# EE474FINAL.net
KiCad netlist of a schematic drawn in EAGLE
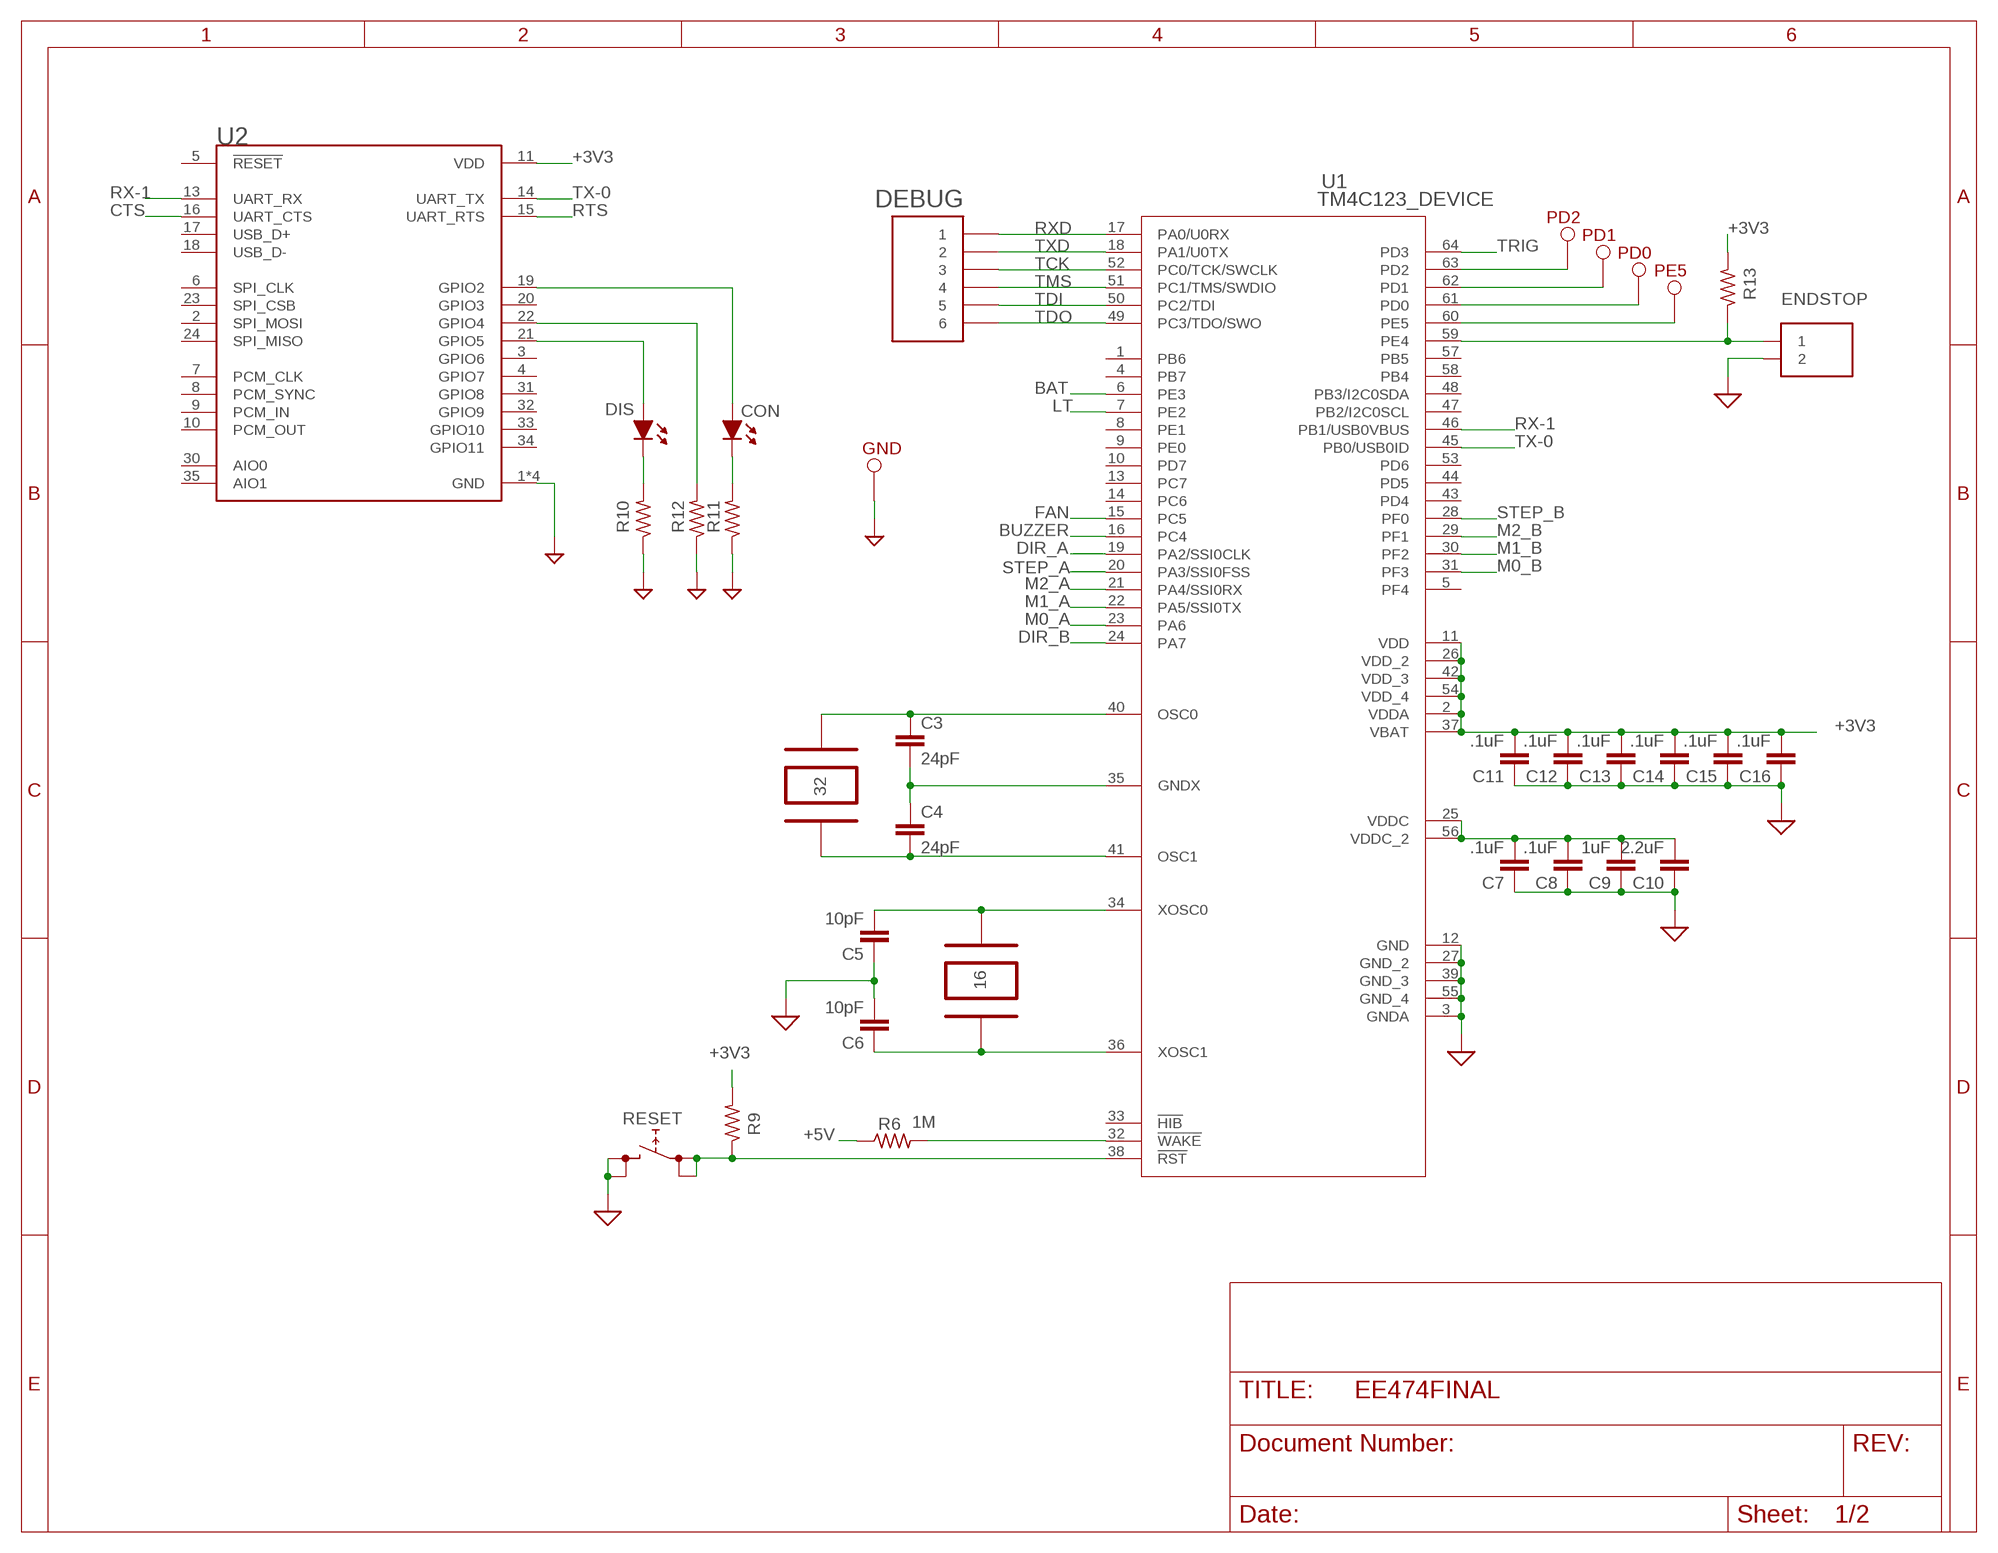
[diagram p0: schematic, sheet 1]
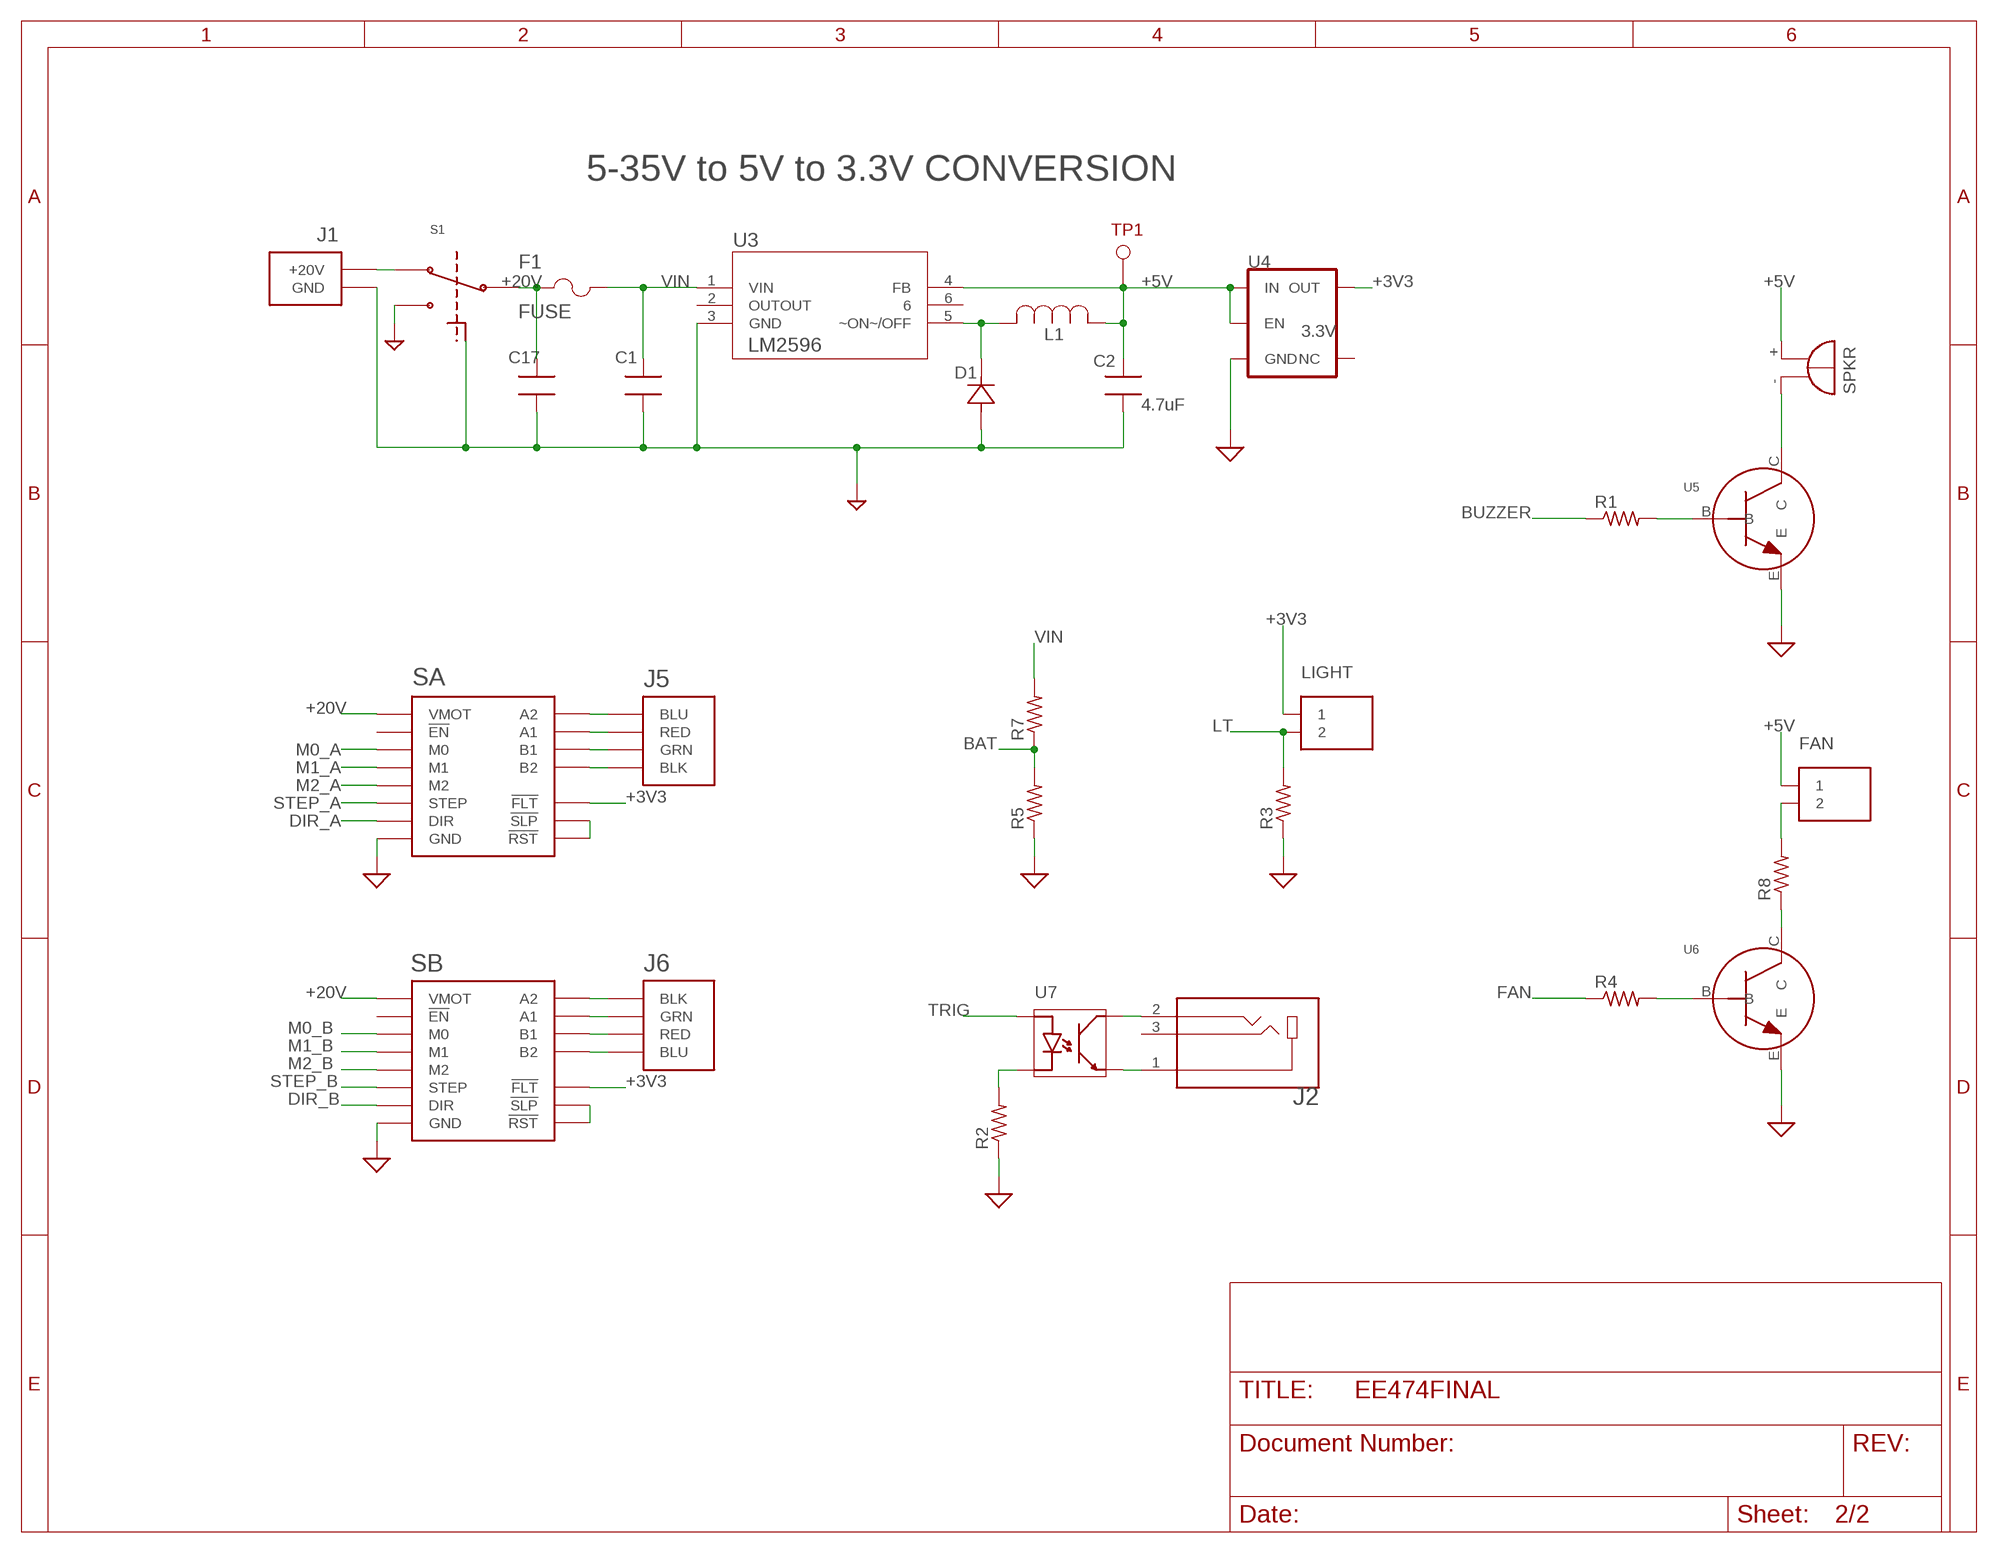
[diagram p1: schematic, sheet 2]

(export (version "E")
  (design (tool "Eeschema 10.0.6"))
  (components
    (comp (ref "C3")
      (value "24pF")
      (footprint "eagle-import:CAPC1005X35N")
      (libsource (lib "eagle-import") (part "CAPACITOR"))
    )
    (comp (ref "C4")
      (value "24pF")
      (footprint "eagle-import:CAPC1005X35N")
      (libsource (lib "eagle-import") (part "CAPACITOR"))
    )
    (comp (ref "C5")
      (value "10pF")
      (footprint "eagle-import:CAPC1005X35N")
      (libsource (lib "eagle-import") (part "CAPACITOR"))
    )
    (comp (ref "C6")
      (value "10pF")
      (footprint "eagle-import:CAPC1005X35N")
      (libsource (lib "eagle-import") (part "CAPACITOR"))
    )
    (comp (ref "C7")
      (value ".1uF")
      (footprint "eagle-import:CAPC1005X35N")
      (libsource (lib "eagle-import") (part "CAPACITOR"))
    )
    (comp (ref "C8")
      (value ".1uF")
      (footprint "eagle-import:CAPC1005X35N")
      (libsource (lib "eagle-import") (part "CAPACITOR"))
    )
    (comp (ref "C9")
      (value "1uF")
      (footprint "eagle-import:CAPC1005X35N")
      (libsource (lib "eagle-import") (part "CAPACITOR"))
    )
    (comp (ref "C10")
      (value "2.2uF")
      (footprint "eagle-import:CAPC1005X35N")
      (libsource (lib "eagle-import") (part "CAPACITOR"))
    )
    (comp (ref "C11")
      (value ".1uF")
      (footprint "eagle-import:CAPC1005X35N")
      (libsource (lib "eagle-import") (part "CAPACITOR"))
    )
    (comp (ref "C12")
      (value ".1uF")
      (footprint "eagle-import:CAPC1005X35N")
      (libsource (lib "eagle-import") (part "CAPACITOR"))
    )
    (comp (ref "C13")
      (value ".1uF")
      (footprint "eagle-import:CAPC1005X35N")
      (libsource (lib "eagle-import") (part "CAPACITOR"))
    )
    (comp (ref "C14")
      (value ".1uF")
      (footprint "eagle-import:CAPC1005X35N")
      (libsource (lib "eagle-import") (part "CAPACITOR"))
    )
    (comp (ref "C15")
      (value ".1uF")
      (footprint "eagle-import:CAPC1005X35N")
      (libsource (lib "eagle-import") (part "CAPACITOR"))
    )
    (comp (ref "C16")
      (value ".1uF")
      (footprint "eagle-import:CAPC1005X35N")
      (libsource (lib "eagle-import") (part "CAPACITOR"))
    )
    (comp (ref "CON")
      (value "LED_511")
      (footprint "eagle-import:LED_511")
      (libsource (lib "eagle-import") (part "LED_511"))
    )
    (comp (ref "DEBUG")
      (value "6POS_JST")
      (footprint "eagle-import:6POS_JST")
      (fields (field (name "MANUFACTURER_PART_NUMBER") "S6BZRLFSN"))
      (libsource (lib "eagle-import") (part "6POS_JST"))
    )
    (comp (ref "DIS")
      (value "LED_511")
      (footprint "eagle-import:LED_511")
      (libsource (lib "eagle-import") (part "LED_511"))
    )
    (comp (ref "ENDSTOP")
      (value "2POS_JSTVERT_2.0")
      (footprint "eagle-import:2POS_JSTVERT_2.00")
      (libsource (lib "eagle-import") (part "2POS_JSTVERT_2.0"))
    )
    (comp (ref "GND")
      (value "TESTPOINT")
      (footprint "eagle-import:TESTPOINT")
      (libsource (lib "eagle-import") (part "TESTPOINT"))
    )
    (comp (ref "PD0")
      (value "TESTPOINT")
      (footprint "eagle-import:TESTPOINT")
      (libsource (lib "eagle-import") (part "TESTPOINT"))
    )
    (comp (ref "PD1")
      (value "TESTPOINT")
      (footprint "eagle-import:TESTPOINT")
      (libsource (lib "eagle-import") (part "TESTPOINT"))
    )
    (comp (ref "PD2")
      (value "TESTPOINT")
      (footprint "eagle-import:TESTPOINT")
      (libsource (lib "eagle-import") (part "TESTPOINT"))
    )
    (comp (ref "PE5")
      (value "TESTPOINT")
      (footprint "eagle-import:TESTPOINT")
      (libsource (lib "eagle-import") (part "TESTPOINT"))
    )
    (comp (ref "R6")
      (value "1M")
      (footprint "eagle-import:CAPC1005X35N")
      (libsource (lib "eagle-import") (part "RESISTOR"))
    )
    (comp (ref "R9")
      (value "RESISTOR")
      (footprint "eagle-import:CAPC1005X35N")
      (libsource (lib "eagle-import") (part "RESISTOR"))
    )
    (comp (ref "R10")
      (value "RESISTOR")
      (footprint "eagle-import:CAPC1005X35N")
      (libsource (lib "eagle-import") (part "RESISTOR"))
    )
    (comp (ref "R11")
      (value "RESISTOR")
      (footprint "eagle-import:CAPC1005X35N")
      (libsource (lib "eagle-import") (part "RESISTOR"))
    )
    (comp (ref "R12")
      (value "RESISTOR")
      (footprint "eagle-import:CAPC1005X35N")
      (libsource (lib "eagle-import") (part "RESISTOR"))
    )
    (comp (ref "R13")
      (value "RESISTOR")
      (footprint "eagle-import:CAPC1005X35N")
      (libsource (lib "eagle-import") (part "RESISTOR"))
    )
    (comp (ref "RESET")
      (value "SWITCH_B3S")
      (footprint "eagle-import:SW_BS3")
      (libsource (lib "eagle-import") (part "SWITCH_B3S"))
    )
    (comp (ref "U1")
      (value "TM4C123_DEVICE")
      (footprint "eagle-import:TM3C123_FOOTPRINT")
      (libsource (lib "eagle-import") (part "TM4C123_DEVICE"))
    )
    (comp (ref "U2")
      (value "RN42-I/RM")
      (footprint "eagle-import:XCVR_RN42-I_RM")
      (fields (field (name "DIGI-KEY_PART_NUMBER") "740-1038-ND") (field (name "MF") "Microchip"))
      (libsource (lib "eagle-import") (part "RN42-I/RM"))
    )
    (comp (ref "Y1")
      (value "32kHz")
      (footprint "eagle-import:GHI2_CRYSTAL_3.2X1.5")
      (libsource (lib "eagle-import") (part "32KHZ_OSCILATOR"))
    )
    (comp (ref "Y2")
      (value "Y2")
      (footprint "eagle-import:CRYSTAL_16MHZ")
      (libsource (lib "eagle-import") (part "16MHZ_OSCILLATOR"))
    )
    (comp (ref "C1")
      (value "CAP_18")
      (footprint "eagle-import:CAP_ULH_10X10")
      (fields (field (name "MANUFACTURER_PART_NUMBER") "ULT2D180MNL1GS"))
      (libsource (lib "eagle-import") (part "CAP_18"))
    )
    (comp (ref "C2")
      (value "4.7uF")
      (footprint "eagle-import:CAP_UCD_8X6P2")
      (fields (field (name "MANUFACTURER_PART_NUMBER") "UUX2A4R7MCL1GS"))
      (libsource (lib "eagle-import") (part "CAP_4.7"))
    )
    (comp (ref "C17")
      (value "CAP_18")
      (footprint "eagle-import:CAP_ULH_10X10")
      (fields (field (name "MANUFACTURER_PART_NUMBER") "ULT2D180MNL1GS"))
      (libsource (lib "eagle-import") (part "CAP_18"))
    )
    (comp (ref "D1")
      (value "DIODE_SHOTKY_SMA")
      (footprint "eagle-import:SMA")
      (fields (field (name "MANUFACTURER_PART_NUMBER") "S1M13F"))
      (libsource (lib "eagle-import") (part "DIODE_SHOTKY_SMA"))
    )
    (comp (ref "F1")
      (value "FUSE")
      (footprint "eagle-import:FUS_VISHAY_MFU0805")
      (fields (field (name "MANUFACTURER_PART_NUMBER") "MFU0805FF02000P100"))
      (libsource (lib "eagle-import") (part "FUSE"))
    )
    (comp (ref "FAN")
      (value "2POS_JSTVERT_2.0")
      (footprint "eagle-import:2POS_JSTVERT_2.00")
      (libsource (lib "eagle-import") (part "2POS_JSTVERT_2.0"))
    )
    (comp (ref "J1")
      (value "2POS_JSTVERT_2.5")
      (footprint "eagle-import:2POS_JSTVERT")
      (libsource (lib "eagle-import") (part "2POS_JSTVERT_2.5"))
    )
    (comp (ref "J2")
      (value "AUDIOJACK")
      (footprint "eagle-import:AUDIOJACK")
      (fields (field (name "MF") "CUI Devices") (field (name "MP") "SJ1-3523N"))
      (libsource (lib "eagle-import") (part "AUDIOJACK"))
    )
    (comp (ref "J5")
      (value "4POS_MOLEXVERT")
      (footprint "eagle-import:4POS_MOLEXVERT")
      (libsource (lib "eagle-import") (part "4POS_MOLEXVERT"))
    )
    (comp (ref "J6")
      (value "4POS_MOLEX_2.54")
      (footprint "eagle-import:MOLEX_0705530003")
      (libsource (lib "eagle-import") (part "4POS_MOLEX_2.54"))
    )
    (comp (ref "L1")
      (value "INDUCTOR_SRR1210-680M")
      (footprint "eagle-import:IND_BOURNS_SRR1210")
      (fields (field (name "MANUFACTURER_PART_NUMBER") "SRR1210680M"))
      (libsource (lib "eagle-import") (part "INDUCTOR_SRR1210-680M"))
    )
    (comp (ref "LIGHT")
      (value "2POS_JSTVERT_2.0")
      (footprint "eagle-import:2POS_JSTVERT_2.00")
      (libsource (lib "eagle-import") (part "2POS_JSTVERT_2.0"))
    )
    (comp (ref "R1")
      (value "R-US_R0402")
      (footprint "eagle-import:R0402")
      (libsource (lib "eagle-import") (part "R-US_R0402"))
    )
    (comp (ref "R2")
      (value "R-US_R0402")
      (footprint "eagle-import:R0402")
      (libsource (lib "eagle-import") (part "R-US_R0402"))
    )
    (comp (ref "R3")
      (value "R-US_R0402")
      (footprint "eagle-import:R0402")
      (libsource (lib "eagle-import") (part "R-US_R0402"))
    )
    (comp (ref "R4")
      (value "R-US_R0402")
      (footprint "eagle-import:R0402")
      (libsource (lib "eagle-import") (part "R-US_R0402"))
    )
    (comp (ref "R5")
      (value "R-US_R0402")
      (footprint "eagle-import:R0402")
      (libsource (lib "eagle-import") (part "R-US_R0402"))
    )
    (comp (ref "R7")
      (value "R-US_R0402")
      (footprint "eagle-import:R0402")
      (libsource (lib "eagle-import") (part "R-US_R0402"))
    )
    (comp (ref "R8")
      (value "R-US_R0402")
      (footprint "eagle-import:R0402")
      (libsource (lib "eagle-import") (part "R-US_R0402"))
    )
    (comp (ref "S1")
      (value "SLIDESWITCH")
      (footprint "eagle-import:SLIDESWITCH")
      (libsource (lib "eagle-import") (part "SLIDESWITCH"))
    )
    (comp (ref "SA")
      (value "DRV8825")
      (footprint "eagle-import:DRV8825")
      (libsource (lib "eagle-import") (part "DRV8825"))
    )
    (comp (ref "SB")
      (value "DRV8825")
      (footprint "eagle-import:DRV8825")
      (libsource (lib "eagle-import") (part "DRV8825"))
    )
    (comp (ref "SPKR")
      (value "F/QMBIII")
      (footprint "eagle-import:F_QMBIII")
      (libsource (lib "eagle-import") (part "F/QMBIII"))
    )
    (comp (ref "TP1")
      (value "TESTPOINT")
      (footprint "eagle-import:TESTPOINT")
      (libsource (lib "eagle-import") (part "TESTPOINT"))
    )
    (comp (ref "U3")
      (value "LM2596SX-5.0/NOPB")
      (footprint "eagle-import:TS5B")
      (fields (field (name "MANUFACTURER_PART_NUMBER") "LM2596SX5.0NOPB"))
      (libsource (lib "eagle-import") (part "LM2596SX-5.0/NOPB"))
    )
    (comp (ref "U4")
      (value "3.3V")
      (footprint "eagle-import:SOT23-5")
      (libsource (lib "eagle-import") (part "V_REG_AP2112K-3.3V"))
    )
    (comp (ref "U5")
      (value "NPN_BJT")
      (footprint "eagle-import:SOT-23")
      (libsource (lib "eagle-import") (part "NPN_BJT"))
    )
    (comp (ref "U6")
      (value "NPN_BJT")
      (footprint "eagle-import:SOT-23")
      (libsource (lib "eagle-import") (part "NPN_BJT"))
    )
    (comp (ref "U7")
      (value "OPTOISOLATOR")
      (footprint "eagle-import:SOP-4L_TC")
      (libsource (lib "eagle-import") (part "OPTOISOLATOR"))
    )
  )
  (nets
    (net (code "1") (name "+3V3") (class "Default")
      (node (ref "C11") (pin "2") (pinfunction "2_2") (pintype "passive"))
      (node (ref "C12") (pin "2") (pinfunction "2_2") (pintype "passive"))
      (node (ref "C13") (pin "2") (pinfunction "2_2") (pintype "passive"))
      (node (ref "C14") (pin "2") (pinfunction "2_2") (pintype "passive"))
      (node (ref "C15") (pin "2") (pinfunction "2_2") (pintype "passive"))
      (node (ref "C16") (pin "2") (pinfunction "2_2") (pintype "passive"))
      (node (ref "LIGHT") (pin "1") (pinfunction "1_1") (pintype "bidirectional"))
      (node (ref "R13") (pin "2") (pinfunction "2_2") (pintype "passive"))
      (node (ref "R9") (pin "2") (pinfunction "2_2") (pintype "passive"))
      (node (ref "SA") (pin "!FLT") (pinfunction "~{FLT}_!FLT") (pintype "bidirectional"))
      (node (ref "SB") (pin "!FLT") (pinfunction "~{FLT}_!FLT") (pintype "bidirectional"))
      (node (ref "U1") (pin "11") (pinfunction "VDD_11") (pintype "power_in"))
      (node (ref "U1") (pin "2") (pinfunction "VDDA_2") (pintype "power_in"))
      (node (ref "U1") (pin "26") (pinfunction "VDD_2_26") (pintype "power_in"))
      (node (ref "U1") (pin "37") (pinfunction "VBAT_37") (pintype "power_in"))
      (node (ref "U1") (pin "42") (pinfunction "VDD_3_42") (pintype "power_in"))
      (node (ref "U1") (pin "54") (pinfunction "VDD_4_54") (pintype "power_in"))
      (node (ref "U2") (pin "11") (pinfunction "VDD_11") (pintype "power_in"))
      (node (ref "U4") (pin "5") (pinfunction "OUT_5") (pintype "passive"))
    )
    (net (code "2") (name "+5V") (class "Default")
      (node (ref "C2") (pin "1") (pinfunction "1_1") (pintype "passive"))
      (node (ref "FAN") (pin "1") (pinfunction "1_1") (pintype "bidirectional"))
      (node (ref "L1") (pin "1") (pinfunction "1_1") (pintype "passive"))
      (node (ref "R6") (pin "1") (pinfunction "1_1") (pintype "passive"))
      (node (ref "SPKR") (pin "+") (pinfunction "-_+") (pintype "passive"))
      (node (ref "TP1") (pin "P$1") (pinfunction "P$1_P$1") (pintype "bidirectional"))
      (node (ref "U3") (pin "4") (pinfunction "FB_4") (pintype "passive"))
      (node (ref "U4") (pin "1") (pinfunction "IN_1") (pintype "input"))
      (node (ref "U4") (pin "3") (pinfunction "EN_3") (pintype "input"))
    )
    (net (code "3") (name "+20V") (class "Default")
      (node (ref "C17") (pin "1") (pinfunction "1_1") (pintype "passive"))
      (node (ref "F1") (pin "1") (pinfunction "1_1") (pintype "passive"))
      (node (ref "S1") (pin "2") (pinfunction "2_2") (pintype "passive"))
      (node (ref "SA") (pin "VMOT") (pinfunction "VMOT_VMOT") (pintype "bidirectional"))
      (node (ref "SB") (pin "VMOT") (pinfunction "VMOT_VMOT") (pintype "bidirectional"))
    )
    (net (code "4") (name "BAT") (class "Default")
      (node (ref "R5") (pin "2") (pinfunction "2_2") (pintype "passive"))
      (node (ref "R7") (pin "1") (pinfunction "1_1") (pintype "passive"))
      (node (ref "U1") (pin "6") (pinfunction "PE3_6") (pintype "bidirectional"))
    )
    (net (code "5") (name "BUZZER") (class "Default")
      (node (ref "R1") (pin "1") (pinfunction "1_1") (pintype "passive"))
      (node (ref "U1") (pin "16") (pinfunction "PC4_16") (pintype "bidirectional"))
    )
    (net (code "6") (name "CTS") (class "Default")
      (node (ref "U2") (pin "16") (pinfunction "UART_CTS_16") (pintype "input"))
    )
    (net (code "7") (name "DIR_A") (class "Default")
      (node (ref "SA") (pin "DIR") (pinfunction "DIR_DIR") (pintype "bidirectional"))
      (node (ref "U1") (pin "19") (pinfunction "PA2/SSI0CLK_19") (pintype "bidirectional"))
    )
    (net (code "8") (name "DIR_B") (class "Default")
      (node (ref "SB") (pin "DIR") (pinfunction "DIR_DIR") (pintype "bidirectional"))
      (node (ref "U1") (pin "24") (pinfunction "PA7_24") (pintype "bidirectional"))
    )
    (net (code "9") (name "FAN") (class "Default")
      (node (ref "R4") (pin "1") (pinfunction "1_1") (pintype "passive"))
      (node (ref "U1") (pin "15") (pinfunction "PC5_15") (pintype "bidirectional"))
    )
    (net (code "10") (name "GND") (class "Default")
      (node (ref "C1") (pin "2") (pinfunction "2_2") (pintype "passive"))
      (node (ref "C10") (pin "1") (pinfunction "1_1") (pintype "passive"))
      (node (ref "C11") (pin "1") (pinfunction "1_1") (pintype "passive"))
      (node (ref "C12") (pin "1") (pinfunction "1_1") (pintype "passive"))
      (node (ref "C13") (pin "1") (pinfunction "1_1") (pintype "passive"))
      (node (ref "C14") (pin "1") (pinfunction "1_1") (pintype "passive"))
      (node (ref "C15") (pin "1") (pinfunction "1_1") (pintype "passive"))
      (node (ref "C16") (pin "1") (pinfunction "1_1") (pintype "passive"))
      (node (ref "C17") (pin "2") (pinfunction "2_2") (pintype "passive"))
      (node (ref "C2") (pin "2") (pinfunction "2_2") (pintype "passive"))
      (node (ref "C5") (pin "1") (pinfunction "1_1") (pintype "passive"))
      (node (ref "C6") (pin "2") (pinfunction "2_2") (pintype "passive"))
      (node (ref "C7") (pin "1") (pinfunction "1_1") (pintype "passive"))
      (node (ref "C8") (pin "1") (pinfunction "1_1") (pintype "passive"))
      (node (ref "C9") (pin "1") (pinfunction "1_1") (pintype "passive"))
      (node (ref "D1") (pin "2") (pinfunction "2_2") (pintype "passive"))
      (node (ref "ENDSTOP") (pin "2") (pinfunction "2_2") (pintype "bidirectional"))
      (node (ref "GND") (pin "P$1") (pinfunction "P$1_P$1") (pintype "bidirectional"))
      (node (ref "J1") (pin "P$2") (pinfunction "GND_P$2") (pintype "passive"))
      (node (ref "R10") (pin "1") (pinfunction "1_1") (pintype "passive"))
      (node (ref "R11") (pin "1") (pinfunction "1_1") (pintype "passive"))
      (node (ref "R12") (pin "1") (pinfunction "1_1") (pintype "passive"))
      (node (ref "R2") (pin "1") (pinfunction "1_1") (pintype "passive"))
      (node (ref "R3") (pin "1") (pinfunction "1_1") (pintype "passive"))
      (node (ref "R5") (pin "1") (pinfunction "1_1") (pintype "passive"))
      (node (ref "RESET") (pin "3") (pinfunction "3_3") (pintype "passive"))
      (node (ref "RESET") (pin "4") (pinfunction "4_4") (pintype "passive"))
      (node (ref "S1") (pin "3") (pinfunction "3_3") (pintype "passive"))
      (node (ref "S1") (pin "4") (pinfunction "GND_4") (pintype "passive"))
      (node (ref "S1") (pin "5") (pinfunction "GND_5") (pintype "passive"))
      (node (ref "SA") (pin "GND$1") (pinfunction "GND_GND$1") (pintype "bidirectional"))
      (node (ref "SA") (pin "GND$2") (pinfunction "GND_GND$2") (pintype "bidirectional"))
      (node (ref "SB") (pin "GND$1") (pinfunction "GND_GND$1") (pintype "bidirectional"))
      (node (ref "SB") (pin "GND$2") (pinfunction "GND_GND$2") (pintype "bidirectional"))
      (node (ref "U1") (pin "12") (pinfunction "GND_12") (pintype "power_in"))
      (node (ref "U1") (pin "27") (pinfunction "GND_2_27") (pintype "power_in"))
      (node (ref "U1") (pin "3") (pinfunction "GNDA_3") (pintype "power_in"))
      (node (ref "U1") (pin "39") (pinfunction "GND_3_39") (pintype "power_in"))
      (node (ref "U1") (pin "55") (pinfunction "GND_4_55") (pintype "power_in"))
      (node (ref "U2") (pin "1") (pinfunction "GND_1") (pintype "power_in"))
      (node (ref "U2") (pin "12") (pinfunction "GND_12") (pintype "power_in"))
      (node (ref "U2") (pin "28") (pinfunction "GND_28") (pintype "power_in"))
      (node (ref "U2") (pin "29") (pinfunction "GND_29") (pintype "power_in"))
      (node (ref "U3") (pin "3") (pinfunction "GND_3") (pintype "passive"))
      (node (ref "U4") (pin "2") (pinfunction "GND_2") (pintype "input"))
      (node (ref "U5") (pin "E") (pinfunction "E_E") (pintype "bidirectional"))
      (node (ref "U6") (pin "E") (pinfunction "E_E") (pintype "bidirectional"))
    )
    (net (code "11") (name "LT") (class "Default")
      (node (ref "LIGHT") (pin "2") (pinfunction "2_2") (pintype "bidirectional"))
      (node (ref "R3") (pin "2") (pinfunction "2_2") (pintype "passive"))
      (node (ref "U1") (pin "7") (pinfunction "PE2_7") (pintype "bidirectional"))
    )
    (net (code "12") (name "M0_A") (class "Default")
      (node (ref "SA") (pin "M0") (pinfunction "M0_M0") (pintype "bidirectional"))
      (node (ref "U1") (pin "23") (pinfunction "PA6_23") (pintype "bidirectional"))
    )
    (net (code "13") (name "M0_B") (class "Default")
      (node (ref "SB") (pin "M0") (pinfunction "M0_M0") (pintype "bidirectional"))
      (node (ref "U1") (pin "31") (pinfunction "PF3_31") (pintype "bidirectional"))
    )
    (net (code "14") (name "M1_A") (class "Default")
      (node (ref "SA") (pin "M1") (pinfunction "M1_M1") (pintype "bidirectional"))
      (node (ref "U1") (pin "22") (pinfunction "PA5/SSI0TX_22") (pintype "bidirectional"))
    )
    (net (code "15") (name "M1_B") (class "Default")
      (node (ref "SB") (pin "M1") (pinfunction "M1_M1") (pintype "bidirectional"))
      (node (ref "U1") (pin "30") (pinfunction "PF2_30") (pintype "bidirectional"))
    )
    (net (code "16") (name "M2_A") (class "Default")
      (node (ref "SA") (pin "M2") (pinfunction "M2_M2") (pintype "bidirectional"))
      (node (ref "U1") (pin "21") (pinfunction "PA4/SSI0RX_21") (pintype "bidirectional"))
    )
    (net (code "17") (name "M2_B") (class "Default")
      (node (ref "SB") (pin "M2") (pinfunction "M2_M2") (pintype "bidirectional"))
      (node (ref "U1") (pin "29") (pinfunction "PF1_29") (pintype "bidirectional"))
    )
    (net (code "18") (name "Net-(CON-1)") (class "Default")
      (node (ref "CON") (pin "P$1") (pinfunction "1_P$1") (pintype "bidirectional"))
      (node (ref "R11") (pin "2") (pinfunction "2_2") (pintype "passive"))
    )
    (net (code "19") (name "Net-(CON-2)") (class "Default")
      (node (ref "CON") (pin "P$2") (pinfunction "2_P$2") (pintype "bidirectional"))
      (node (ref "U2") (pin "19") (pinfunction "GPIO2_19") (pintype "bidirectional"))
    )
    (net (code "20") (name "Net-(DIS-1)") (class "Default")
      (node (ref "DIS") (pin "P$1") (pinfunction "1_P$1") (pintype "bidirectional"))
      (node (ref "R10") (pin "2") (pinfunction "2_2") (pintype "passive"))
    )
    (net (code "21") (name "Net-(DIS-2)") (class "Default")
      (node (ref "DIS") (pin "P$2") (pinfunction "2_P$2") (pintype "bidirectional"))
      (node (ref "U2") (pin "21") (pinfunction "GPIO5_21") (pintype "bidirectional"))
    )
    (net (code "22") (name "Net-(FAN-Pad2)") (class "Default")
      (node (ref "FAN") (pin "2") (pinfunction "2_2") (pintype "bidirectional"))
      (node (ref "R8") (pin "2") (pinfunction "2_2") (pintype "passive"))
    )
    (net (code "23") (name "Net-(J1-+20V)") (class "Default")
      (node (ref "J1") (pin "P$1") (pinfunction "+20V_P$1") (pintype "passive"))
      (node (ref "S1") (pin "1") (pinfunction "1_1") (pintype "passive"))
    )
    (net (code "24") (name "Net-(J2-Pad1)") (class "Default")
      (node (ref "J2") (pin "1") (pinfunction "1_1") (pintype "passive"))
      (node (ref "U7") (pin "3") (pinfunction "3_3") (pintype "bidirectional"))
    )
    (net (code "25") (name "Net-(J2-Pad2)") (class "Default")
      (node (ref "J2") (pin "2") (pinfunction "2_2") (pintype "passive"))
      (node (ref "U7") (pin "4") (pinfunction "4_4") (pintype "bidirectional"))
    )
    (net (code "26") (name "Net-(J5-BLK)") (class "Default")
      (node (ref "J5") (pin "P$1") (pinfunction "BLK_P$1") (pintype "bidirectional"))
      (node (ref "SA") (pin "B2") (pinfunction "B2_B2") (pintype "bidirectional"))
    )
    (net (code "27") (name "Net-(J5-BLU)") (class "Default")
      (node (ref "J5") (pin "P$4") (pinfunction "BLU_P$4") (pintype "bidirectional"))
      (node (ref "SA") (pin "A2") (pinfunction "A2_A2") (pintype "bidirectional"))
    )
    (net (code "28") (name "Net-(J5-GRN)") (class "Default")
      (node (ref "J5") (pin "P$2") (pinfunction "GRN_P$2") (pintype "bidirectional"))
      (node (ref "SA") (pin "B1") (pinfunction "B1_B1") (pintype "bidirectional"))
    )
    (net (code "29") (name "Net-(J5-RED)") (class "Default")
      (node (ref "J5") (pin "P$3") (pinfunction "RED_P$3") (pintype "bidirectional"))
      (node (ref "SA") (pin "A1") (pinfunction "A1_A1") (pintype "bidirectional"))
    )
    (net (code "30") (name "Net-(J6-BLK)") (class "Default")
      (node (ref "J6") (pin "4") (pinfunction "BLK_4") (pintype "bidirectional"))
      (node (ref "SB") (pin "A2") (pinfunction "A2_A2") (pintype "bidirectional"))
    )
    (net (code "31") (name "Net-(J6-BLU)") (class "Default")
      (node (ref "J6") (pin "1") (pinfunction "BLU_1") (pintype "bidirectional"))
      (node (ref "SB") (pin "B2") (pinfunction "B2_B2") (pintype "bidirectional"))
    )
    (net (code "32") (name "Net-(J6-GRN)") (class "Default")
      (node (ref "J6") (pin "3") (pinfunction "GRN_3") (pintype "bidirectional"))
      (node (ref "SB") (pin "A1") (pinfunction "A1_A1") (pintype "bidirectional"))
    )
    (net (code "33") (name "Net-(J6-RED)") (class "Default")
      (node (ref "J6") (pin "2") (pinfunction "RED_2") (pintype "bidirectional"))
      (node (ref "SB") (pin "B1") (pinfunction "B1_B1") (pintype "bidirectional"))
    )
    (net (code "34") (name "Net-(R1-Pad2)") (class "Default")
      (node (ref "R1") (pin "2") (pinfunction "2_2") (pintype "passive"))
      (node (ref "U5") (pin "B") (pinfunction "B_B") (pintype "bidirectional"))
    )
    (net (code "35") (name "Net-(R2-Pad2)") (class "Default")
      (node (ref "R2") (pin "2") (pinfunction "2_2") (pintype "passive"))
      (node (ref "U7") (pin "2") (pinfunction "2_2") (pintype "bidirectional"))
    )
    (net (code "36") (name "Net-(R4-Pad2)") (class "Default")
      (node (ref "R4") (pin "2") (pinfunction "2_2") (pintype "passive"))
      (node (ref "U6") (pin "B") (pinfunction "B_B") (pintype "bidirectional"))
    )
    (net (code "37") (name "Net-(R8-Pad1)") (class "Default")
      (node (ref "R8") (pin "1") (pinfunction "1_1") (pintype "passive"))
      (node (ref "U6") (pin "C") (pinfunction "C_C") (pintype "bidirectional"))
    )
    (net (code "38") (name "Net-(SA-~{RST})") (class "Default")
      (node (ref "SA") (pin "!RST") (pinfunction "~{RST}_!RST") (pintype "bidirectional"))
      (node (ref "SA") (pin "!SLP") (pinfunction "~{SLP}_!SLP") (pintype "bidirectional"))
    )
    (net (code "39") (name "Net-(SB-~{RST})") (class "Default")
      (node (ref "SB") (pin "!RST") (pinfunction "~{RST}_!RST") (pintype "bidirectional"))
      (node (ref "SB") (pin "!SLP") (pinfunction "~{SLP}_!SLP") (pintype "bidirectional"))
    )
    (net (code "40") (name "Net-(SPKR-+)") (class "Default")
      (node (ref "SPKR") (pin "-") (pinfunction "+_-") (pintype "passive"))
      (node (ref "U5") (pin "C") (pinfunction "C_C") (pintype "bidirectional"))
    )
    (net (code "41") (name "Net-(U1-GNDX)") (class "Default")
      (node (ref "C3") (pin "2") (pinfunction "2_2") (pintype "passive"))
      (node (ref "C4") (pin "1") (pinfunction "1_1") (pintype "passive"))
      (node (ref "U1") (pin "35") (pinfunction "GNDX_35") (pintype "power_in"))
    )
    (net (code "42") (name "Net-(U1-OSC0)") (class "Default")
      (node (ref "C3") (pin "1") (pinfunction "1_1") (pintype "passive"))
      (node (ref "U1") (pin "40") (pinfunction "OSC0_40") (pintype "input"))
      (node (ref "Y1") (pin "P$2") (pinfunction "2_P$2") (pintype "passive"))
    )
    (net (code "43") (name "Net-(U1-OSC1)") (class "Default")
      (node (ref "C4") (pin "2") (pinfunction "2_2") (pintype "passive"))
      (node (ref "U1") (pin "41") (pinfunction "OSC1_41") (pintype "output"))
      (node (ref "Y1") (pin "P$1") (pinfunction "1_P$1") (pintype "passive"))
    )
    (net (code "44") (name "Net-(U1-PD0)") (class "Default")
      (node (ref "PD0") (pin "P$1") (pinfunction "P$1_P$1") (pintype "bidirectional"))
      (node (ref "U1") (pin "61") (pinfunction "PD0_61") (pintype "bidirectional"))
    )
    (net (code "45") (name "Net-(U1-PD1)") (class "Default")
      (node (ref "PD1") (pin "P$1") (pinfunction "P$1_P$1") (pintype "bidirectional"))
      (node (ref "U1") (pin "62") (pinfunction "PD1_62") (pintype "bidirectional"))
    )
    (net (code "46") (name "Net-(U1-PD2)") (class "Default")
      (node (ref "PD2") (pin "P$1") (pinfunction "P$1_P$1") (pintype "bidirectional"))
      (node (ref "U1") (pin "63") (pinfunction "PD2_63") (pintype "bidirectional"))
    )
    (net (code "47") (name "Net-(U1-PE4)") (class "Default")
      (node (ref "ENDSTOP") (pin "1") (pinfunction "1_1") (pintype "bidirectional"))
      (node (ref "R13") (pin "1") (pinfunction "1_1") (pintype "passive"))
      (node (ref "U1") (pin "59") (pinfunction "PE4_59") (pintype "bidirectional"))
    )
    (net (code "48") (name "Net-(U1-PE5)") (class "Default")
      (node (ref "PE5") (pin "P$1") (pinfunction "P$1_P$1") (pintype "bidirectional"))
      (node (ref "U1") (pin "60") (pinfunction "PE5_60") (pintype "bidirectional"))
    )
    (net (code "49") (name "Net-(U1-VDDC)") (class "Default")
      (node (ref "C10") (pin "2") (pinfunction "2_2") (pintype "passive"))
      (node (ref "C7") (pin "2") (pinfunction "2_2") (pintype "passive"))
      (node (ref "C8") (pin "2") (pinfunction "2_2") (pintype "passive"))
      (node (ref "C9") (pin "2") (pinfunction "2_2") (pintype "passive"))
      (node (ref "U1") (pin "25") (pinfunction "VDDC_25") (pintype "power_in"))
      (node (ref "U1") (pin "56") (pinfunction "VDDC_2_56") (pintype "power_in"))
    )
    (net (code "50") (name "Net-(U1-XOSC0)") (class "Default")
      (node (ref "C5") (pin "2") (pinfunction "2_2") (pintype "passive"))
      (node (ref "U1") (pin "34") (pinfunction "XOSC0_34") (pintype "input"))
      (node (ref "Y2") (pin "2") (pinfunction "2_2") (pintype "passive"))
    )
    (net (code "51") (name "Net-(U1-XOSC1)") (class "Default")
      (node (ref "C6") (pin "1") (pinfunction "1_1") (pintype "passive"))
      (node (ref "U1") (pin "36") (pinfunction "XOSC1_36") (pintype "output"))
      (node (ref "Y2") (pin "1") (pinfunction "1_1") (pintype "passive"))
    )
    (net (code "52") (name "Net-(U1-~{RST})") (class "Default")
      (node (ref "R9") (pin "1") (pinfunction "1_1") (pintype "passive"))
      (node (ref "RESET") (pin "1") (pinfunction "1_1") (pintype "passive"))
      (node (ref "RESET") (pin "2") (pinfunction "2_2") (pintype "passive"))
      (node (ref "U1") (pin "38") (pinfunction "~{RST}_38") (pintype "input"))
    )
    (net (code "53") (name "Net-(U1-~{WAKE})") (class "Default")
      (node (ref "R6") (pin "2") (pinfunction "2_2") (pintype "passive"))
      (node (ref "U1") (pin "32") (pinfunction "~{WAKE}_32") (pintype "input"))
    )
    (net (code "54") (name "Net-(U2-GPIO4)") (class "Default")
      (node (ref "R12") (pin "2") (pinfunction "2_2") (pintype "passive"))
      (node (ref "U2") (pin "22") (pinfunction "GPIO4_22") (pintype "bidirectional"))
    )
    (net (code "55") (name "Net-(U3-~{ON}{slash}OFF)") (class "Default")
      (node (ref "D1") (pin "1") (pinfunction "1_1") (pintype "passive"))
      (node (ref "L1") (pin "2") (pinfunction "2_2") (pintype "passive"))
      (node (ref "U3") (pin "5") (pinfunction "~{ON}/OFF_5") (pintype "passive"))
    )
    (net (code "56") (name "RTS") (class "Default")
      (node (ref "U2") (pin "15") (pinfunction "UART_RTS_15") (pintype "output"))
    )
    (net (code "57") (name "RX-1") (class "Default")
      (node (ref "U1") (pin "46") (pinfunction "PB1/USB0VBUS_46") (pintype "bidirectional"))
      (node (ref "U2") (pin "13") (pinfunction "UART_RX_13") (pintype "input"))
    )
    (net (code "58") (name "RXD") (class "Default")
      (node (ref "DEBUG") (pin "6") (pinfunction "1_6") (pintype "bidirectional"))
      (node (ref "U1") (pin "17") (pinfunction "PA0/U0RX_17") (pintype "bidirectional"))
    )
    (net (code "59") (name "STEP_A") (class "Default")
      (node (ref "SA") (pin "STEP") (pinfunction "STEP_STEP") (pintype "bidirectional"))
      (node (ref "U1") (pin "20") (pinfunction "PA3/SSI0FSS_20") (pintype "bidirectional"))
    )
    (net (code "60") (name "STEP_B") (class "Default")
      (node (ref "SB") (pin "STEP") (pinfunction "STEP_STEP") (pintype "bidirectional"))
      (node (ref "U1") (pin "28") (pinfunction "PF0_28") (pintype "bidirectional"))
    )
    (net (code "61") (name "TCK") (class "Default")
      (node (ref "DEBUG") (pin "4") (pinfunction "3_4") (pintype "bidirectional"))
      (node (ref "U1") (pin "52") (pinfunction "PC0/TCK/SWCLK_52") (pintype "bidirectional"))
    )
    (net (code "62") (name "TDI") (class "Default")
      (node (ref "DEBUG") (pin "2") (pinfunction "5_2") (pintype "bidirectional"))
      (node (ref "U1") (pin "50") (pinfunction "PC2/TDI_50") (pintype "bidirectional"))
    )
    (net (code "63") (name "TDO") (class "Default")
      (node (ref "DEBUG") (pin "1") (pinfunction "6_1") (pintype "bidirectional"))
      (node (ref "U1") (pin "49") (pinfunction "PC3/TDO/SWO_49") (pintype "bidirectional"))
    )
    (net (code "64") (name "TMS") (class "Default")
      (node (ref "DEBUG") (pin "3") (pinfunction "4_3") (pintype "bidirectional"))
      (node (ref "U1") (pin "51") (pinfunction "PC1/TMS/SWDIO_51") (pintype "bidirectional"))
    )
    (net (code "65") (name "TRIG") (class "Default")
      (node (ref "U1") (pin "64") (pinfunction "PD3_64") (pintype "bidirectional"))
      (node (ref "U7") (pin "1") (pinfunction "1_1") (pintype "bidirectional"))
    )
    (net (code "66") (name "TX-0") (class "Default")
      (node (ref "U1") (pin "45") (pinfunction "PB0/USB0ID_45") (pintype "bidirectional"))
      (node (ref "U2") (pin "14") (pinfunction "UART_TX_14") (pintype "output"))
    )
    (net (code "67") (name "TXD") (class "Default")
      (node (ref "DEBUG") (pin "5") (pinfunction "2_5") (pintype "bidirectional"))
      (node (ref "U1") (pin "18") (pinfunction "PA1/U0TX_18") (pintype "bidirectional"))
    )
    (net (code "68") (name "VIN") (class "Default")
      (node (ref "C1") (pin "1") (pinfunction "1_1") (pintype "passive"))
      (node (ref "F1") (pin "2") (pinfunction "2_2") (pintype "passive"))
      (node (ref "R7") (pin "2") (pinfunction "2_2") (pintype "passive"))
      (node (ref "U3") (pin "1") (pinfunction "VIN_1") (pintype "input"))
    )
    (net (code "69") (name "unconnected-(J2-Pad3)") (class "Default")
      (node (ref "J2") (pin "3") (pinfunction "3_3") (pintype "passive"))
    )
    (net (code "70") (name "unconnected-(SA-~{EN}-Pad!EN)") (class "Default")
      (node (ref "SA") (pin "!EN") (pinfunction "~{EN}_!EN") (pintype "bidirectional"))
    )
    (net (code "71") (name "unconnected-(SB-~{EN}-Pad!EN)") (class "Default")
      (node (ref "SB") (pin "!EN") (pinfunction "~{EN}_!EN") (pintype "bidirectional"))
    )
    (net (code "72") (name "unconnected-(U1-PB2{slash}I2C0SCL-Pad47)") (class "Default")
      (node (ref "U1") (pin "47") (pinfunction "PB2/I2C0SCL_47") (pintype "bidirectional"))
    )
    (net (code "73") (name "unconnected-(U1-PB3{slash}I2C0SDA-Pad48)") (class "Default")
      (node (ref "U1") (pin "48") (pinfunction "PB3/I2C0SDA_48") (pintype "bidirectional"))
    )
    (net (code "74") (name "unconnected-(U1-PB4-Pad58)") (class "Default")
      (node (ref "U1") (pin "58") (pinfunction "PB4_58") (pintype "bidirectional"))
    )
    (net (code "75") (name "unconnected-(U1-PB5-Pad57)") (class "Default")
      (node (ref "U1") (pin "57") (pinfunction "PB5_57") (pintype "bidirectional"))
    )
    (net (code "76") (name "unconnected-(U1-PB6-Pad1)") (class "Default")
      (node (ref "U1") (pin "1") (pinfunction "PB6_1") (pintype "bidirectional"))
    )
    (net (code "77") (name "unconnected-(U1-PB7-Pad4)") (class "Default")
      (node (ref "U1") (pin "4") (pinfunction "PB7_4") (pintype "bidirectional"))
    )
    (net (code "78") (name "unconnected-(U1-PC6-Pad14)") (class "Default")
      (node (ref "U1") (pin "14") (pinfunction "PC6_14") (pintype "bidirectional"))
    )
    (net (code "79") (name "unconnected-(U1-PC7-Pad13)") (class "Default")
      (node (ref "U1") (pin "13") (pinfunction "PC7_13") (pintype "bidirectional"))
    )
    (net (code "80") (name "unconnected-(U1-PD4-Pad43)") (class "Default")
      (node (ref "U1") (pin "43") (pinfunction "PD4_43") (pintype "bidirectional"))
    )
    (net (code "81") (name "unconnected-(U1-PD5-Pad44)") (class "Default")
      (node (ref "U1") (pin "44") (pinfunction "PD5_44") (pintype "bidirectional"))
    )
    (net (code "82") (name "unconnected-(U1-PD6-Pad53)") (class "Default")
      (node (ref "U1") (pin "53") (pinfunction "PD6_53") (pintype "bidirectional"))
    )
    (net (code "83") (name "unconnected-(U1-PD7-Pad10)") (class "Default")
      (node (ref "U1") (pin "10") (pinfunction "PD7_10") (pintype "bidirectional"))
    )
    (net (code "84") (name "unconnected-(U1-PE0-Pad9)") (class "Default")
      (node (ref "U1") (pin "9") (pinfunction "PE0_9") (pintype "bidirectional"))
    )
    (net (code "85") (name "unconnected-(U1-PE1-Pad8)") (class "Default")
      (node (ref "U1") (pin "8") (pinfunction "PE1_8") (pintype "bidirectional"))
    )
    (net (code "86") (name "unconnected-(U1-PF4-Pad5)") (class "Default")
      (node (ref "U1") (pin "5") (pinfunction "PF4_5") (pintype "bidirectional"))
    )
    (net (code "87") (name "unconnected-(U1-~{HIB}-Pad33)") (class "Default")
      (node (ref "U1") (pin "33") (pinfunction "~{HIB}_33") (pintype "output"))
    )
    (net (code "88") (name "unconnected-(U2-AIO0-Pad30)") (class "Default")
      (node (ref "U2") (pin "30") (pinfunction "AIO0_30") (pintype "bidirectional"))
    )
    (net (code "89") (name "unconnected-(U2-AIO1-Pad35)") (class "Default")
      (node (ref "U2") (pin "35") (pinfunction "AIO1_35") (pintype "bidirectional"))
    )
    (net (code "90") (name "unconnected-(U2-GPIO3-Pad20)") (class "Default")
      (node (ref "U2") (pin "20") (pinfunction "GPIO3_20") (pintype "bidirectional"))
    )
    (net (code "91") (name "unconnected-(U2-GPIO6-Pad3)") (class "Default")
      (node (ref "U2") (pin "3") (pinfunction "GPIO6_3") (pintype "bidirectional"))
    )
    (net (code "92") (name "unconnected-(U2-GPIO7-Pad4)") (class "Default")
      (node (ref "U2") (pin "4") (pinfunction "GPIO7_4") (pintype "bidirectional"))
    )
    (net (code "93") (name "unconnected-(U2-GPIO8-Pad31)") (class "Default")
      (node (ref "U2") (pin "31") (pinfunction "GPIO8_31") (pintype "bidirectional"))
    )
    (net (code "94") (name "unconnected-(U2-GPIO9-Pad32)") (class "Default")
      (node (ref "U2") (pin "32") (pinfunction "GPIO9_32") (pintype "bidirectional"))
    )
    (net (code "95") (name "unconnected-(U2-GPIO10-Pad33)") (class "Default")
      (node (ref "U2") (pin "33") (pinfunction "GPIO10_33") (pintype "bidirectional"))
    )
    (net (code "96") (name "unconnected-(U2-GPIO11-Pad34)") (class "Default")
      (node (ref "U2") (pin "34") (pinfunction "GPIO11_34") (pintype "bidirectional"))
    )
    (net (code "97") (name "unconnected-(U2-PCM_CLK-Pad7)") (class "Default")
      (node (ref "U2") (pin "7") (pinfunction "PCM_CLK_7") (pintype "bidirectional"))
    )
    (net (code "98") (name "unconnected-(U2-PCM_IN-Pad9)") (class "Default")
      (node (ref "U2") (pin "9") (pinfunction "PCM_IN_9") (pintype "input"))
    )
    (net (code "99") (name "unconnected-(U2-PCM_OUT-Pad10)") (class "Default")
      (node (ref "U2") (pin "10") (pinfunction "PCM_OUT_10") (pintype "output"))
    )
    (net (code "100") (name "unconnected-(U2-PCM_SYNC-Pad8)") (class "Default")
      (node (ref "U2") (pin "8") (pinfunction "PCM_SYNC_8") (pintype "bidirectional"))
    )
    (net (code "101") (name "unconnected-(U2-SPI_CLK-Pad6)") (class "Default")
      (node (ref "U2") (pin "6") (pinfunction "SPI_CLK_6") (pintype "input"))
    )
    (net (code "102") (name "unconnected-(U2-SPI_CSB-Pad23)") (class "Default")
      (node (ref "U2") (pin "23") (pinfunction "SPI_CSB_23") (pintype "input"))
    )
    (net (code "103") (name "unconnected-(U2-SPI_MISO-Pad24)") (class "Default")
      (node (ref "U2") (pin "24") (pinfunction "SPI_MISO_24") (pintype "output"))
    )
    (net (code "104") (name "unconnected-(U2-SPI_MOSI-Pad2)") (class "Default")
      (node (ref "U2") (pin "2") (pinfunction "SPI_MOSI_2") (pintype "input"))
    )
    (net (code "105") (name "unconnected-(U2-USB_D+-Pad17)") (class "Default")
      (node (ref "U2") (pin "17") (pinfunction "USB_D+_17") (pintype "bidirectional"))
    )
    (net (code "106") (name "unconnected-(U2-USB_D--Pad18)") (class "Default")
      (node (ref "U2") (pin "18") (pinfunction "USB_D-_18") (pintype "bidirectional"))
    )
    (net (code "107") (name "unconnected-(U2-~{RESET}-Pad5)") (class "Default")
      (node (ref "U2") (pin "5") (pinfunction "~{RESET}_5") (pintype "input"))
    )
    (net (code "108") (name "unconnected-(U3-OUTOUT-Pad2)") (class "Default")
      (node (ref "U3") (pin "2") (pinfunction "OUTOUT_2") (pintype "output"))
    )
    (net (code "109") (name "unconnected-(U3-Pad6)") (class "Default")
      (node (ref "U3") (pin "6") (pinfunction "6_6") (pintype "passive"))
    )
    (net (code "110") (name "unconnected-(U4-NC-Pad4)") (class "Default")
      (node (ref "U4") (pin "4") (pinfunction "NC_4") (pintype "no_connect"))
    )
  )
)
